# MRCS-RelayBreakout.net
KiCad netlist of a schematic drawn in EAGLE
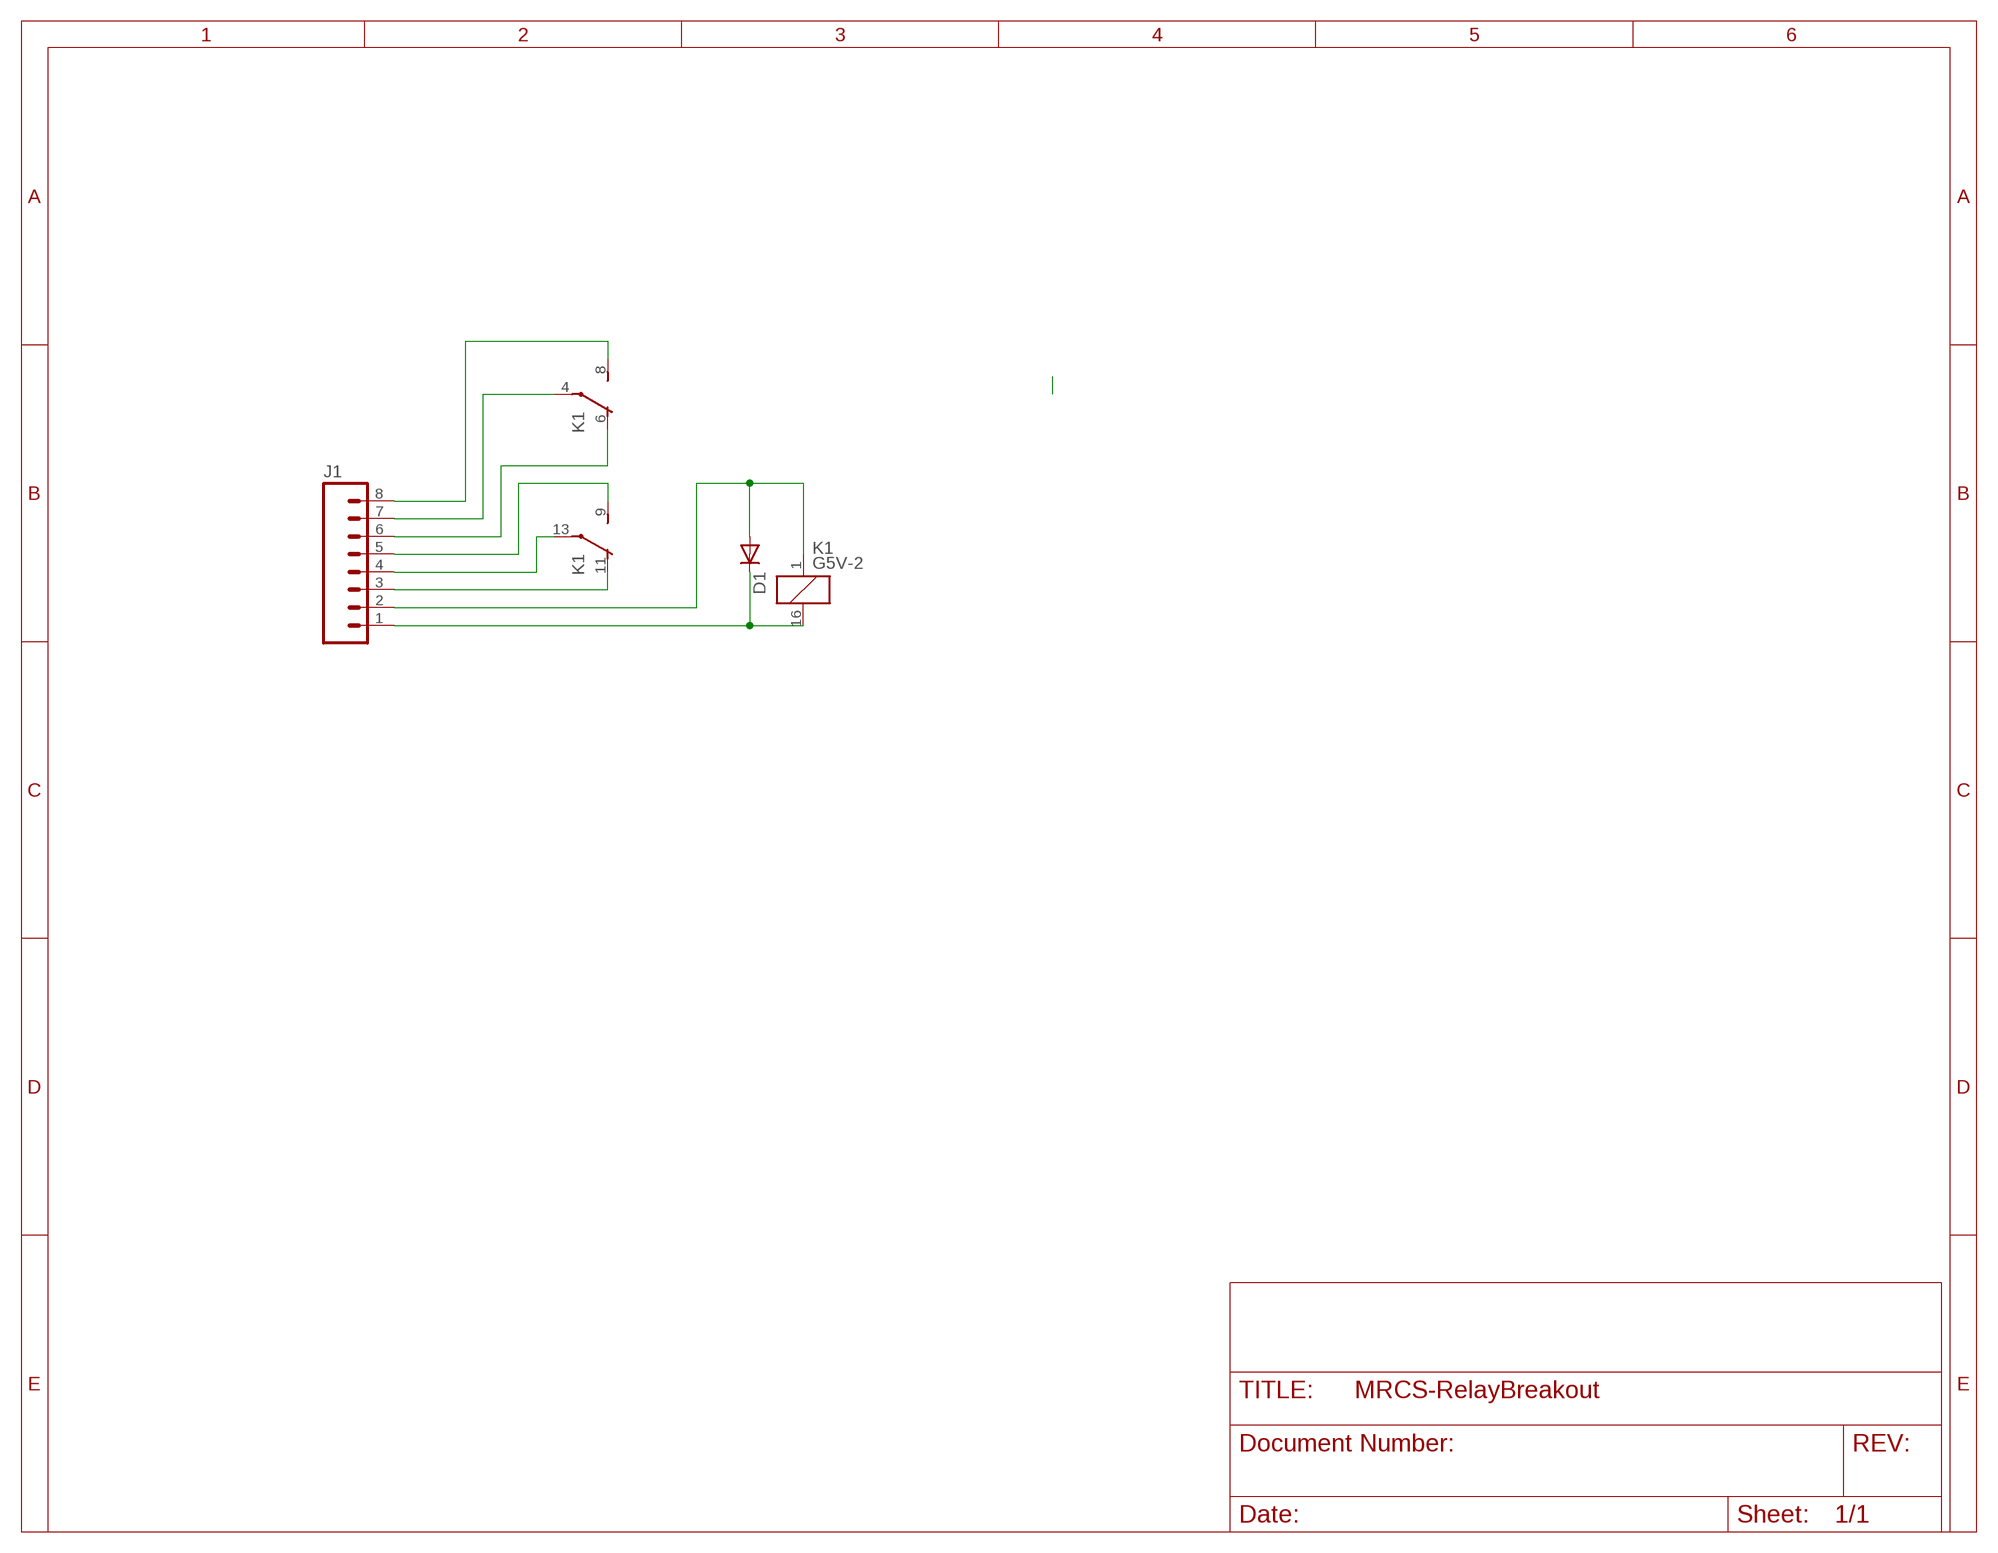
[diagram p0: schematic, sheet 1]

(export (version "E")
  (design (tool "Eeschema 10.0.6"))
  (components
    (comp (ref "D1")
      (value "DIODEPTH")
      (footprint "eagle-import:DIODE-1N4001")
      (libsource (lib "eagle-import") (part "DIODEPTH"))
    )
    (comp (ref "J1")
      (value "CONNECTOR-M08LOCK")
      (footprint "eagle-import:1X08_LOCK")
      (libsource (lib "eagle-import") (part "CONNECTOR-M08LOCK"))
    )
    (comp (ref "K1")
      (value "G5V-2")
      (footprint "eagle-import:G5V-2")
      (fields (field (name "MPN") "G5V-2 5DC"))
      (libsource (lib "eagle-import") (part "G5V-2"))
    )
  )
  (nets
    (net (code "1") (name "Net-(D1-PadA)") (class "Default")
      (node (ref "D1") (pin "A") (pinfunction "A_A") (pintype "passive"))
      (node (ref "J1") (pin "2") (pinfunction "2_2") (pintype "passive"))
      (node (ref "K1") (pin "1") (pinfunction "1_1") (pintype "passive"))
    )
    (net (code "2") (name "Net-(K1A-O)") (class "Default")
      (node (ref "J1") (pin "6") (pinfunction "6_6") (pintype "passive"))
      (node (ref "K1") (pin "6") (pinfunction "O_6") (pintype "passive"))
    )
    (net (code "3") (name "Net-(K1A-P)") (class "Default")
      (node (ref "J1") (pin "7") (pinfunction "7_7") (pintype "passive"))
      (node (ref "K1") (pin "4") (pinfunction "P_4") (pintype "passive"))
    )
    (net (code "4") (name "Net-(K1A-S)") (class "Default")
      (node (ref "J1") (pin "8") (pinfunction "8_8") (pintype "passive"))
      (node (ref "K1") (pin "8") (pinfunction "S_8") (pintype "passive"))
    )
    (net (code "5") (name "Net-(K1B-O)") (class "Default")
      (node (ref "J1") (pin "3") (pinfunction "3_3") (pintype "passive"))
      (node (ref "K1") (pin "11") (pinfunction "O_11") (pintype "passive"))
    )
    (net (code "6") (name "Net-(K1B-P)") (class "Default")
      (node (ref "J1") (pin "4") (pinfunction "4_4") (pintype "passive"))
      (node (ref "K1") (pin "13") (pinfunction "P_13") (pintype "passive"))
    )
    (net (code "7") (name "Net-(K1B-S)") (class "Default")
      (node (ref "J1") (pin "5") (pinfunction "5_5") (pintype "passive"))
      (node (ref "K1") (pin "9") (pinfunction "S_9") (pintype "passive"))
    )
    (net (code "8") (name "Net-(K1C-2)") (class "Default")
      (node (ref "D1") (pin "C") (pinfunction "C_C") (pintype "passive"))
      (node (ref "J1") (pin "1") (pinfunction "1_1") (pintype "passive"))
      (node (ref "K1") (pin "16") (pinfunction "2_16") (pintype "passive"))
    )
  )
)
